# CC2541A.net
KiCad netlist of a schematic drawn in Altium Designer
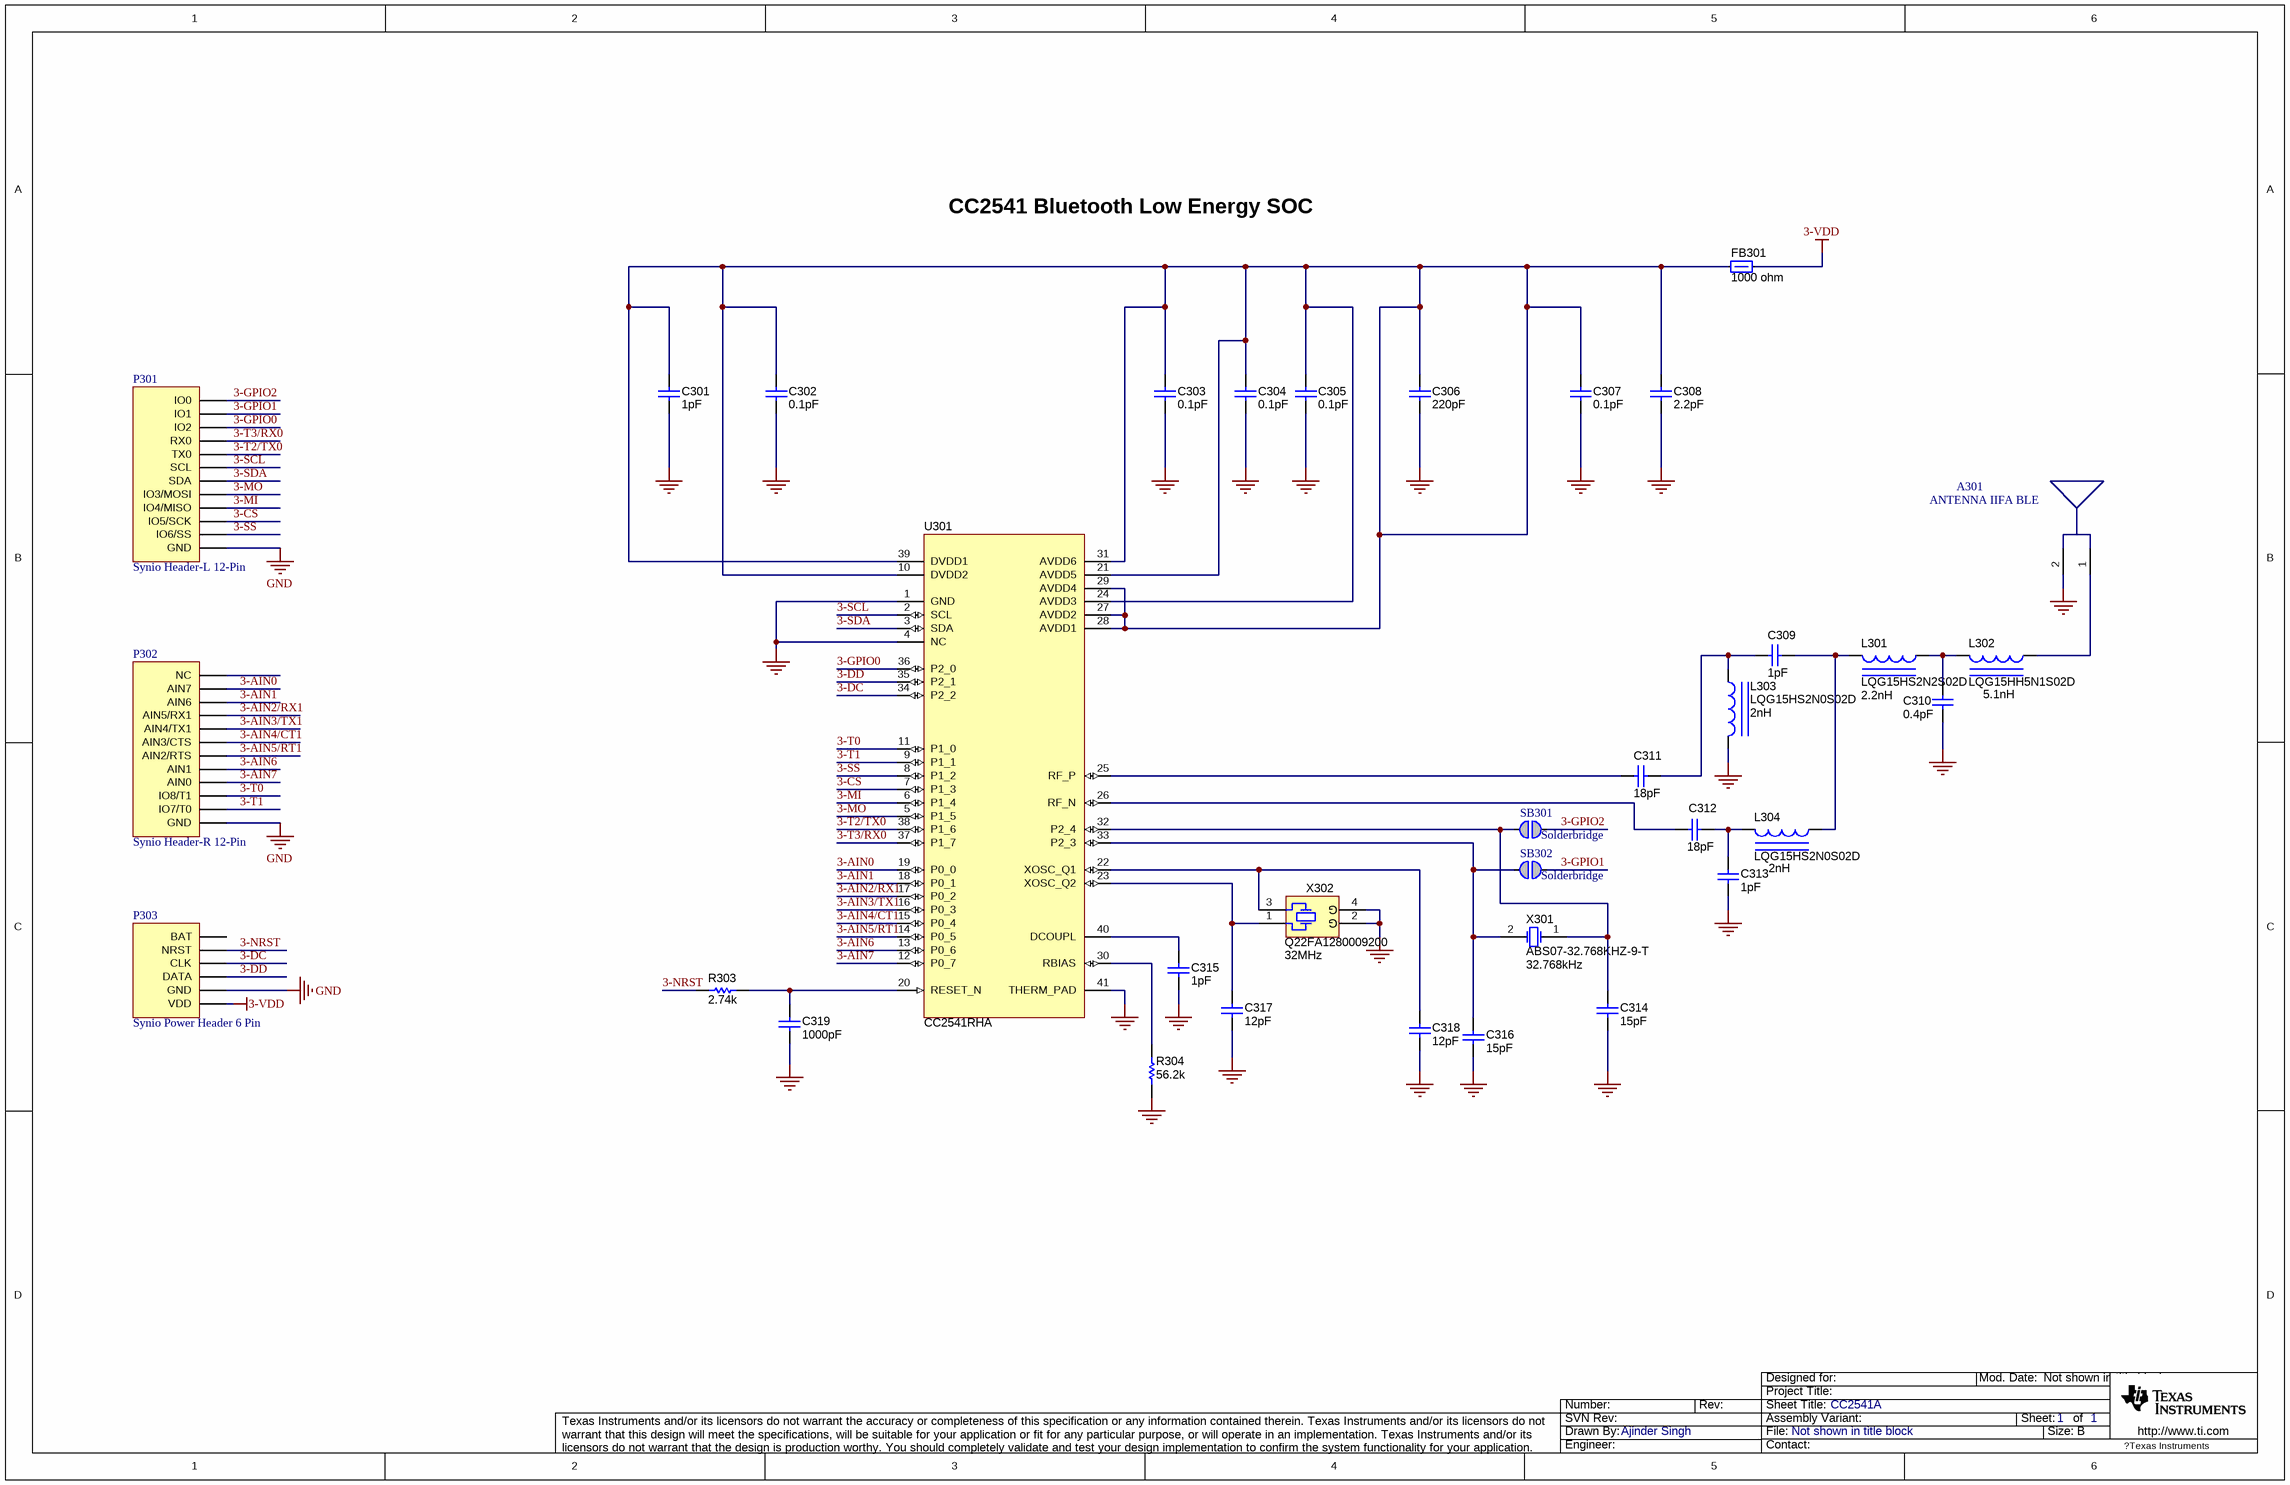
[diagram p0: CC2541A.SchDoc]

(export (version "E")
  (design (tool "Eeschema 10.0.6"))
  (components
    (comp (ref "A301")
      (value "ANTENNA IIFA BLE")
      (footprint "Antenna_IIFA_BLE-2")
      (libsource (lib "Schematic_Library") (part "ANTENNA"))
    )
    (comp (ref "C301")
      (value "C1005X5R0J105M")
      (footprint "0402L")
      (description "CAP, CERM, 1uF, 6.3V, +/-20%, X5R, 0402")
      (fields
        (field (name "VALUEDISPLAYED") "1pF")
        (field (name "MANUFACTURER") "TDK")
        (field (name "PUBLISHER") "Texas Instruments")
      )
      (libsource (lib "Capacitor_Ceramic") (part "C1005X5R0J105M"))
    )
    (comp (ref "C302")
      (value "GRM155R71A104KA01D")
      (footprint "0402L")
      (description "CAP, CERM, 0.1uF, 10V, +/-10%, X7R, 0402")
      (fields
        (field (name "VALUEDISPLAYED") "0.1pF")
        (field (name "MANUFACTURER") "MuRata")
        (field (name "PUBLISHER") "Texas Instruments")
      )
      (libsource (lib "Capacitor_Ceramic") (part "GRM155R71A104KA01D"))
    )
    (comp (ref "C303")
      (value "GRM155R71A104KA01D")
      (footprint "0402L")
      (description "CAP, CERM, 0.1uF, 10V, +/-10%, X7R, 0402")
      (fields
        (field (name "VALUEDISPLAYED") "0.1pF")
        (field (name "MANUFACTURER") "MuRata")
        (field (name "PUBLISHER") "Texas Instruments")
      )
      (libsource (lib "Capacitor_Ceramic") (part "GRM155R71A104KA01D"))
    )
    (comp (ref "C304")
      (value "GRM155R71A104KA01D")
      (footprint "0402L")
      (description "CAP, CERM, 0.1uF, 10V, +/-10%, X7R, 0402")
      (fields
        (field (name "VALUEDISPLAYED") "0.1pF")
        (field (name "MANUFACTURER") "MuRata")
        (field (name "PUBLISHER") "Texas Instruments")
      )
      (libsource (lib "Capacitor_Ceramic") (part "GRM155R71A104KA01D"))
    )
    (comp (ref "C305")
      (value "GRM155R71A104KA01D")
      (footprint "0402L")
      (description "CAP, CERM, 0.1uF, 10V, +/-10%, X7R, 0402")
      (fields
        (field (name "VALUEDISPLAYED") "0.1pF")
        (field (name "MANUFACTURER") "MuRata")
        (field (name "PUBLISHER") "Texas Instruments")
      )
      (libsource (lib "Capacitor_Ceramic") (part "GRM155R71A104KA01D"))
    )
    (comp (ref "C306")
      (value "GRM1555C1H221JA01D")
      (footprint "0402L")
      (description "CAP, CERM, 220pF, 50V, +/-5%, C0G/NP0, 0402")
      (fields
        (field (name "VALUEDISPLAYED") "220pF")
        (field (name "MANUFACTURER") "MuRata")
        (field (name "PUBLISHER") "Texas Instruments")
      )
      (libsource (lib "Capacitor_Ceramic") (part "GRM1555C1H221JA01D"))
    )
    (comp (ref "C307")
      (value "GRM155R71A104KA01D")
      (footprint "0402L")
      (description "CAP, CERM, 0.1uF, 10V, +/-10%, X7R, 0402")
      (fields
        (field (name "VALUEDISPLAYED") "0.1pF")
        (field (name "MANUFACTURER") "MuRata")
        (field (name "PUBLISHER") "Texas Instruments")
      )
      (libsource (lib "Capacitor_Ceramic") (part "GRM155R71A104KA01D"))
    )
    (comp (ref "C308")
      (value "JMK105BJ225MV-F")
      (footprint "0402L")
      (description "CAP, CERM, 2.2uF, 6.3V, +/-20%, X5R, 0402")
      (fields
        (field (name "VALUEDISPLAYED") "2.2pF")
        (field (name "MANUFACTURER") "Taiyo Yuden")
        (field (name "PUBLISHER") "Texas Instruments")
      )
      (libsource (lib "Capacitor_Ceramic") (part "JMK105BJ225MV-F"))
    )
    (comp (ref "C309")
      (value "GRM1555C1H1R0CA01D")
      (footprint "0402L")
      (description "CAP, CERM, 1pF, 50V, +/-5%, C0G/NP0, 0402")
      (fields
        (field (name "VALUEDISPLAYED") "1pF")
        (field (name "MANUFACTURER") "MuRata")
        (field (name "PUBLISHER") "Texas Instruments")
      )
      (libsource (lib "Capacitor_Ceramic") (part "GRM1555C1H1R0CA01D"))
    )
    (comp (ref "C310")
      (value "GRM1555C1HR40BA01D")
      (footprint "0402L")
      (description "CAP, CERM, 0.4pF, 50V, +/-25%, C0G/NP0, 0402")
      (fields
        (field (name "VALUEDISPLAYED") "0.4pF")
        (field (name "MANUFACTURER") "MuRata")
        (field (name "PUBLISHER") "Texas Instruments")
      )
      (libsource (lib "Capacitor_Ceramic") (part "GRM1555C1HR40BA01D"))
    )
    (comp (ref "C311")
      (value "GRM1555C1H180JA01D")
      (footprint "0402L")
      (description "CAP, CERM, 18pF, 50V, +/-5%, C0G/NP0, 0402")
      (fields
        (field (name "VALUEDISPLAYED") "18pF")
        (field (name "MANUFACTURER") "MuRata")
        (field (name "PUBLISHER") "Texas Instruments")
      )
      (libsource (lib "Capacitor_Ceramic") (part "GRM1555C1H180JA01D"))
    )
    (comp (ref "C312")
      (value "GRM1555C1H180JA01D")
      (footprint "0402L")
      (description "CAP, CERM, 18pF, 50V, +/-5%, C0G/NP0, 0402")
      (fields
        (field (name "VALUEDISPLAYED") "18pF")
        (field (name "MANUFACTURER") "MuRata")
        (field (name "PUBLISHER") "Texas Instruments")
      )
      (libsource (lib "Capacitor_Ceramic") (part "GRM1555C1H180JA01D"))
    )
    (comp (ref "C313")
      (value "GRM1555C1H1R0CA01D")
      (footprint "0402L")
      (description "CAP, CERM, 1pF, 50V, +/-5%, C0G/NP0, 0402")
      (fields
        (field (name "VALUEDISPLAYED") "1pF")
        (field (name "MANUFACTURER") "MuRata")
        (field (name "PUBLISHER") "Texas Instruments")
      )
      (libsource (lib "Capacitor_Ceramic") (part "GRM1555C1H1R0CA01D"))
    )
    (comp (ref "C314")
      (value "GRM1555C1H150JA01D")
      (footprint "0402L")
      (description "CAP, CERM, 15pF, 50V, +/-5%, C0G/NP0, 0402")
      (fields
        (field (name "VALUEDISPLAYED") "15pF")
        (field (name "MANUFACTURER") "MuRata")
        (field (name "PUBLISHER") "Texas Instruments")
      )
      (libsource (lib "Capacitor_Ceramic") (part "GRM1555C1H150JA01D"))
    )
    (comp (ref "C315")
      (value "C1005X5R0J105M")
      (footprint "0402L")
      (description "CAP, CERM, 1uF, 6.3V, +/-20%, X5R, 0402")
      (fields
        (field (name "VALUEDISPLAYED") "1pF")
        (field (name "MANUFACTURER") "TDK")
        (field (name "PUBLISHER") "Texas Instruments")
      )
      (libsource (lib "Capacitor_Ceramic") (part "C1005X5R0J105M"))
    )
    (comp (ref "C316")
      (value "GRM1555C1H150JA01D")
      (footprint "0402L")
      (description "CAP, CERM, 15pF, 50V, +/-5%, C0G/NP0, 0402")
      (fields
        (field (name "VALUEDISPLAYED") "15pF")
        (field (name "MANUFACTURER") "MuRata")
        (field (name "PUBLISHER") "Texas Instruments")
      )
      (libsource (lib "Capacitor_Ceramic") (part "GRM1555C1H150JA01D"))
    )
    (comp (ref "C317")
      (value "GRM1555C1H120JA01D")
      (footprint "0402L")
      (description "CAP, CERM, 12pF, 50V, +/-5%, C0G/NP0, 0402")
      (fields
        (field (name "VALUEDISPLAYED") "12pF")
        (field (name "MANUFACTURER") "MuRata")
        (field (name "PUBLISHER") "Texas Instruments")
      )
      (libsource (lib "Capacitor_Ceramic") (part "GRM1555C1H120JA01D"))
    )
    (comp (ref "C318")
      (value "GRM1555C1H120JA01D")
      (footprint "0402L")
      (description "CAP, CERM, 12pF, 50V, +/-5%, C0G/NP0, 0402")
      (fields
        (field (name "VALUEDISPLAYED") "12pF")
        (field (name "MANUFACTURER") "MuRata")
        (field (name "PUBLISHER") "Texas Instruments")
      )
      (libsource (lib "Capacitor_Ceramic") (part "GRM1555C1H120JA01D"))
    )
    (comp (ref "C319")
      (value "GRM1555C1H102JA01D")
      (footprint "0402L")
      (description "CAP, CERM, 1000pF, 50V, +/-5%, C0G/NP0, 0402")
      (fields
        (field (name "VALUEDISPLAYED") "1000pF")
        (field (name "MANUFACTURER") "MuRata")
        (field (name "PUBLISHER") "Texas Instruments")
      )
      (libsource (lib "Capacitor_Ceramic") (part "GRM1555C1H102JA01D"))
    )
    (comp (ref "FB301")
      (value "1000 ohm")
      (footprint "0402")
      (description "0.25A Ferrite Bead, 1000 ohm @ 100MHz, SMD")
      (fields
        (field (name "PARTNUMBER") "BLM15HG102SN1D")
        (field (name "MANUFACTURER") "MuRata")
        (field (name "PUBLISHER") "Texas Instruments")
      )
      (libsource (lib "Inductor") (part "BLM15HG102SN1D"))
    )
    (comp (ref "L301")
      (value "LQG15HS2N2S02D")
      (footprint "IND_LQG15H")
      (description "Inductor, Multilayer, Air Core, 2.2nH, 0.3A, 0.12 ohm, SMD")
      (fields
        (field (name "VALUEDISPLAYED") "2.2nH")
        (field (name "MANUFACTURER") "MuRata")
        (field (name "PUBLISHER") "Texas Instruments")
      )
      (libsource (lib "Inductor") (part "LQG15HS2N2S02D"))
    )
    (comp (ref "L302")
      (value "LQG15HH5N1S02D")
      (footprint "0402L")
      (description "Inductor, Multilayer, Ferrite, 5.1nH, 0.3A, 0.2 ohm, SMD")
      (fields
        (field (name "VALUEDISPLAYED") "5.1nH")
        (field (name "MANUFACTURER") "MuRata")
        (field (name "PUBLISHER") "Texas Instruments")
      )
      (libsource (lib "Inductor") (part "LQG15HH5N1S02D"))
    )
    (comp (ref "L303")
      (value "LQG15HS2N0S02D")
      (footprint "0402L")
      (description "Inductor, Multilayer, Ferrite, 2nH, 0.3A, 0.1 ohm, SMD")
      (fields
        (field (name "VALUEDISPLAYED") "2nH")
        (field (name "MANUFACTURER") "MuRata")
        (field (name "PUBLISHER") "Texas Instruments")
      )
      (libsource (lib "Inductor") (part "LQG15HS2N0S02D"))
    )
    (comp (ref "L304")
      (value "LQG15HS2N0S02D")
      (footprint "0402L")
      (description "Inductor, Multilayer, Ferrite, 2nH, 0.3A, 0.1 ohm, SMD")
      (fields
        (field (name "VALUEDISPLAYED") "2nH")
        (field (name "MANUFACTURER") "MuRata")
        (field (name "PUBLISHER") "Texas Instruments")
      )
      (libsource (lib "Inductor") (part "LQG15HS2N0S02D"))
    )
    (comp (ref "P301")
      (value "Synio Header-L 12-Pin")
      (footprint "HDR1X12")
      (description "Synio Header-L, 12-Pin")
      (fields (field (name "PUBLISHER") "Altium Limited"))
      (libsource (lib "Connector") (part "Synio Header-L 12-Pin"))
    )
    (comp (ref "P302")
      (value "Synio Header-R 12-Pin")
      (footprint "HDR1X12")
      (description "Synio Header-R, 12-Pin")
      (fields (field (name "PUBLISHER") "Altium Limited"))
      (libsource (lib "Connector") (part "Synio Header-R 12-Pin"))
    )
    (comp (ref "P303")
      (value "Synio Power Header 6 Pin")
      (footprint "HDR1X6/2.54MM")
      (libsource (lib "Connector") (part "Synio Power Header 6 Pin"))
    )
    (comp (ref "R303")
      (value "2.74k")
      (footprint "0402L")
      (description "RES, 2.74k ohm, 1%, 0.063W, 0402")
      (fields
        (field (name "PARTNUMBER") "CRCW04022K74FKED")
        (field (name "MANUFACTURER") "Vishay-Dale")
        (field (name "PUBLISHER") "Texas Instruments")
      )
      (libsource (lib "Resistor_0402") (part "CRCW04022K74FKED"))
    )
    (comp (ref "R304")
      (value "56.2k")
      (footprint "0402L")
      (description "RES, 56.2k ohm, 1%, 0.063W, 0402")
      (fields
        (field (name "PARTNUMBER") "CRCW040256K2FKED")
        (field (name "MANUFACTURER") "Vishay-Dale")
        (field (name "PUBLISHER") "Texas Instruments")
      )
      (libsource (lib "Resistor_0402") (part "CRCW040256K2FKED"))
    )
    (comp (ref "SB301")
      (value "Solderbridge")
      (footprint "JP2_SMD")
      (fields (field (name "PUBLISHER") "Nordic Semiconductor"))
      (libsource (lib "Nordic Passive DB") (part "SOLDERBRIDGE"))
    )
    (comp (ref "SB302")
      (value "Solderbridge")
      (footprint "JP2_SMD")
      (fields (field (name "PUBLISHER") "Nordic Semiconductor"))
      (libsource (lib "Nordic Passive DB") (part "SOLDERBRIDGE"))
    )
    (comp (ref "U301")
      (value "CC2541RHA")
      (footprint "RHA0040H")
      (description "2.4-GHz Bluetooth low energy and Proprietary System-on-Chip, RHA0040H")
      (fields
        (field (name "MANUFACTURER") "Texas Instruments")
        (field (name "SYMBOLCREATOR") "a0411947")
        (field (name "PUBLISHER") "Texas Instruments")
      )
      (libsource (lib "TI_Pre_Release") (part "CC2541RHA"))
    )
    (comp (ref "X301")
      (value "ABS07-32.768KHZ-9-T")
      (footprint "XTAL_ABS07")
      (description "CRYSTAL, 32.768KHZ, 9PF, SMD")
      (fields
        (field (name "FREQUENCY") "32.768kHz")
        (field (name "MANUFACTURER") "Abracon Corportation")
        (field (name "SYMBOLCREATOR") "a0412235")
        (field (name "PUBLISHER") "Texas Instruments")
      )
      (libsource (lib "Oscillators") (part "ABS07-32.768KHZ-9-T"))
    )
    (comp (ref "X302")
      (value "Q22FA1280009200")
      (footprint "XTAL_FA-128")
      (description "Crystal, 32MHz, 10pF, SMD")
      (fields
        (field (name "FREQUENCY") "32MHz")
        (field (name "MANUFACTURER") "Epson")
        (field (name "SYMBOLCREATOR") "a0412235")
        (field (name "PUBLISHER") "Texas Instruments")
      )
      (libsource (lib "Oscillators") (part "Q22FA1280009200"))
    )
  )
  (nets
    (net (code "1") (name "/3-AIN0") (class "Default")
      (node (ref "P302") (pin "11") (pinfunction "AIN7_11") (pintype "passive"))
      (node (ref "U301") (pin "19") (pinfunction "P0_0_19") (pintype "bidirectional"))
    )
    (net (code "2") (name "/3-AIN1") (class "Default")
      (node (ref "P302") (pin "10") (pinfunction "AIN6_10") (pintype "passive"))
      (node (ref "U301") (pin "18") (pinfunction "P0_1_18") (pintype "bidirectional"))
    )
    (net (code "3") (name "/3-AIN2{slash}RX1") (class "Default")
      (node (ref "P302") (pin "9") (pinfunction "AIN5/RX1_9") (pintype "passive"))
      (node (ref "U301") (pin "17") (pinfunction "P0_2_17") (pintype "bidirectional"))
    )
    (net (code "4") (name "/3-AIN3{slash}TX1") (class "Default")
      (node (ref "P302") (pin "8") (pinfunction "AIN4/TX1_8") (pintype "passive"))
      (node (ref "U301") (pin "16") (pinfunction "P0_3_16") (pintype "bidirectional"))
    )
    (net (code "5") (name "/3-AIN4{slash}CT1") (class "Default")
      (node (ref "P302") (pin "7") (pinfunction "AIN3/CTS_7") (pintype "passive"))
      (node (ref "U301") (pin "15") (pinfunction "P0_4_15") (pintype "bidirectional"))
    )
    (net (code "6") (name "/3-AIN5{slash}RT1") (class "Default")
      (node (ref "P302") (pin "6") (pinfunction "AIN2/RTS_6") (pintype "passive"))
      (node (ref "U301") (pin "14") (pinfunction "P0_5_14") (pintype "bidirectional"))
    )
    (net (code "7") (name "/3-AIN6") (class "Default")
      (node (ref "P302") (pin "5") (pinfunction "AIN1_5") (pintype "passive"))
      (node (ref "U301") (pin "13") (pinfunction "P0_6_13") (pintype "bidirectional"))
    )
    (net (code "8") (name "/3-AIN7") (class "Default")
      (node (ref "P302") (pin "4") (pinfunction "AIN0_4") (pintype "passive"))
      (node (ref "U301") (pin "12") (pinfunction "P0_7_12") (pintype "bidirectional"))
    )
    (net (code "9") (name "/3-CS") (class "Default")
      (node (ref "P301") (pin "3") (pinfunction "IO5/SCK_3") (pintype "passive"))
      (node (ref "U301") (pin "7") (pinfunction "P1_3_7") (pintype "bidirectional"))
    )
    (net (code "10") (name "/3-DC") (class "Default")
      (node (ref "P303") (pin "4") (pinfunction "CLK_4") (pintype "passive"))
      (node (ref "U301") (pin "34") (pinfunction "P2_2_34") (pintype "bidirectional"))
    )
    (net (code "11") (name "/3-DD") (class "Default")
      (node (ref "P303") (pin "3") (pinfunction "DATA_3") (pintype "passive"))
      (node (ref "U301") (pin "35") (pinfunction "P2_1_35") (pintype "bidirectional"))
    )
    (net (code "12") (name "/3-GPIO0") (class "Default")
      (node (ref "P301") (pin "10") (pinfunction "IO2_10") (pintype "passive"))
      (node (ref "U301") (pin "36") (pinfunction "P2_0_36") (pintype "bidirectional"))
    )
    (net (code "13") (name "/3-GPIO1") (class "Default")
      (node (ref "P301") (pin "11") (pinfunction "IO1_11") (pintype "passive"))
      (node (ref "SB302") (pin "1") (pinfunction "0_1") (pintype "passive"))
    )
    (net (code "14") (name "/3-GPIO2") (class "Default")
      (node (ref "P301") (pin "12") (pinfunction "IO0_12") (pintype "passive"))
      (node (ref "SB301") (pin "1") (pinfunction "0_1") (pintype "passive"))
    )
    (net (code "15") (name "/3-MI") (class "Default")
      (node (ref "P301") (pin "4") (pinfunction "IO4/MISO_4") (pintype "passive"))
      (node (ref "U301") (pin "6") (pinfunction "P1_4_6") (pintype "bidirectional"))
    )
    (net (code "16") (name "/3-MO") (class "Default")
      (node (ref "P301") (pin "5") (pinfunction "IO3/MOSI_5") (pintype "passive"))
      (node (ref "U301") (pin "5") (pinfunction "P1_5_5") (pintype "bidirectional"))
    )
    (net (code "17") (name "/3-NRST") (class "Default")
      (node (ref "P303") (pin "5") (pinfunction "NRST_5") (pintype "passive"))
      (node (ref "R303") (pin "1") (pinfunction "1_1") (pintype "passive"))
    )
    (net (code "18") (name "/3-SCL") (class "Default")
      (node (ref "P301") (pin "7") (pinfunction "SCL_7") (pintype "passive"))
      (node (ref "U301") (pin "2") (pinfunction "SCL_2") (pintype "bidirectional"))
    )
    (net (code "19") (name "/3-SDA") (class "Default")
      (node (ref "P301") (pin "6") (pinfunction "SDA_6") (pintype "passive"))
      (node (ref "U301") (pin "3") (pinfunction "SDA_3") (pintype "bidirectional"))
    )
    (net (code "20") (name "/3-SS") (class "Default")
      (node (ref "P301") (pin "2") (pinfunction "IO6/SS_2") (pintype "passive"))
      (node (ref "U301") (pin "8") (pinfunction "P1_2_8") (pintype "bidirectional"))
    )
    (net (code "21") (name "/3-T0") (class "Default")
      (node (ref "P302") (pin "3") (pinfunction "IO8/T1_3") (pintype "passive"))
      (node (ref "U301") (pin "11") (pinfunction "P1_0_11") (pintype "bidirectional"))
    )
    (net (code "22") (name "/3-T1") (class "Default")
      (node (ref "P302") (pin "2") (pinfunction "IO7/T0_2") (pintype "passive"))
      (node (ref "U301") (pin "9") (pinfunction "P1_1_9") (pintype "bidirectional"))
    )
    (net (code "23") (name "/3-T2{slash}TX0") (class "Default")
      (node (ref "P301") (pin "8") (pinfunction "TX0_8") (pintype "passive"))
      (node (ref "U301") (pin "38") (pinfunction "P1_6_38") (pintype "bidirectional"))
    )
    (net (code "24") (name "/3-T3{slash}RX0") (class "Default")
      (node (ref "P301") (pin "9") (pinfunction "RX0_9") (pintype "passive"))
      (node (ref "U301") (pin "37") (pinfunction "P1_7_37") (pintype "bidirectional"))
    )
    (net (code "25") (name "3-VDD") (class "Default")
      (node (ref "FB301") (pin "2") (pinfunction "2_2") (pintype "passive"))
      (node (ref "P303") (pin "1") (pinfunction "VDD_1") (pintype "passive"))
    )
    (net (code "26") (name "GND") (class "Default")
      (node (ref "A301") (pin "2") (pinfunction "2_2") (pintype "passive"))
      (node (ref "C301") (pin "2") (pinfunction "2_2") (pintype "passive"))
      (node (ref "C302") (pin "2") (pinfunction "2_2") (pintype "passive"))
      (node (ref "C303") (pin "2") (pinfunction "2_2") (pintype "passive"))
      (node (ref "C304") (pin "2") (pinfunction "2_2") (pintype "passive"))
      (node (ref "C305") (pin "2") (pinfunction "2_2") (pintype "passive"))
      (node (ref "C306") (pin "2") (pinfunction "2_2") (pintype "passive"))
      (node (ref "C307") (pin "2") (pinfunction "2_2") (pintype "passive"))
      (node (ref "C308") (pin "2") (pinfunction "2_2") (pintype "passive"))
      (node (ref "C310") (pin "2") (pinfunction "2_2") (pintype "passive"))
      (node (ref "C313") (pin "2") (pinfunction "2_2") (pintype "passive"))
      (node (ref "C314") (pin "2") (pinfunction "2_2") (pintype "passive"))
      (node (ref "C315") (pin "2") (pinfunction "2_2") (pintype "passive"))
      (node (ref "C316") (pin "2") (pinfunction "2_2") (pintype "passive"))
      (node (ref "C317") (pin "2") (pinfunction "2_2") (pintype "passive"))
      (node (ref "C318") (pin "2") (pinfunction "2_2") (pintype "passive"))
      (node (ref "C319") (pin "2") (pinfunction "2_2") (pintype "passive"))
      (node (ref "L303") (pin "2") (pinfunction "2_2") (pintype "passive"))
      (node (ref "P301") (pin "1") (pinfunction "GND_1") (pintype "passive"))
      (node (ref "P302") (pin "1") (pinfunction "GND_1") (pintype "passive"))
      (node (ref "P303") (pin "2") (pinfunction "GND_2") (pintype "passive"))
      (node (ref "R304") (pin "1") (pinfunction "1_1") (pintype "passive"))
      (node (ref "U301") (pin "1") (pinfunction "GND_1") (pintype "power_in"))
      (node (ref "U301") (pin "4") (pinfunction "NC_4") (pintype "passive"))
      (node (ref "U301") (pin "41") (pinfunction "THERM_PAD_41") (pintype "power_in"))
      (node (ref "X302") (pin "2") (pinfunction "GND_2") (pintype "power_in"))
      (node (ref "X302") (pin "4") (pinfunction "GND_4") (pintype "power_in"))
    )
    (net (code "27") (name "Net-(A301-Pad1)") (class "Default")
      (node (ref "A301") (pin "1") (pinfunction "1_1") (pintype "passive"))
      (node (ref "L302") (pin "1") (pinfunction "1_1") (pintype "passive"))
    )
    (net (code "28") (name "Net-(C309-Pad1)") (class "Default")
      (node (ref "C309") (pin "1") (pinfunction "1_1") (pintype "passive"))
      (node (ref "C311") (pin "1") (pinfunction "1_1") (pintype "passive"))
      (node (ref "L303") (pin "1") (pinfunction "1_1") (pintype "passive"))
    )
    (net (code "29") (name "Net-(C309-Pad2)") (class "Default")
      (node (ref "C309") (pin "2") (pinfunction "2_2") (pintype "passive"))
      (node (ref "L301") (pin "2") (pinfunction "2_2") (pintype "passive"))
      (node (ref "L304") (pin "1") (pinfunction "1_1") (pintype "passive"))
    )
    (net (code "30") (name "Net-(C310-Pad1)") (class "Default")
      (node (ref "C310") (pin "1") (pinfunction "1_1") (pintype "passive"))
      (node (ref "L301") (pin "1") (pinfunction "1_1") (pintype "passive"))
      (node (ref "L302") (pin "2") (pinfunction "2_2") (pintype "passive"))
    )
    (net (code "31") (name "Net-(C312-Pad1)") (class "Default")
      (node (ref "C312") (pin "1") (pinfunction "1_1") (pintype "passive"))
      (node (ref "C313") (pin "1") (pinfunction "1_1") (pintype "passive"))
      (node (ref "L304") (pin "2") (pinfunction "2_2") (pintype "passive"))
    )
    (net (code "32") (name "Net-(SB301-1)") (class "Default")
      (node (ref "C314") (pin "1") (pinfunction "1_1") (pintype "passive"))
      (node (ref "SB301") (pin "2") (pinfunction "1_2") (pintype "passive"))
      (node (ref "U301") (pin "32") (pinfunction "P2_4_32") (pintype "bidirectional"))
      (node (ref "X301") (pin "1") (pinfunction "OSC1_1") (pintype "passive"))
    )
    (net (code "33") (name "Net-(SB302-1)") (class "Default")
      (node (ref "C316") (pin "1") (pinfunction "1_1") (pintype "passive"))
      (node (ref "SB302") (pin "2") (pinfunction "1_2") (pintype "passive"))
      (node (ref "U301") (pin "33") (pinfunction "P2_3_33") (pintype "bidirectional"))
      (node (ref "X301") (pin "2") (pinfunction "OSC2_2") (pintype "passive"))
    )
    (net (code "34") (name "Net-(U301-AVDD1)") (class "Default")
      (node (ref "C301") (pin "1") (pinfunction "1_1") (pintype "passive"))
      (node (ref "C302") (pin "1") (pinfunction "1_1") (pintype "passive"))
      (node (ref "C303") (pin "1") (pinfunction "1_1") (pintype "passive"))
      (node (ref "C304") (pin "1") (pinfunction "1_1") (pintype "passive"))
      (node (ref "C305") (pin "1") (pinfunction "1_1") (pintype "passive"))
      (node (ref "C306") (pin "1") (pinfunction "1_1") (pintype "passive"))
      (node (ref "C307") (pin "1") (pinfunction "1_1") (pintype "passive"))
      (node (ref "C308") (pin "1") (pinfunction "1_1") (pintype "passive"))
      (node (ref "FB301") (pin "1") (pinfunction "1_1") (pintype "passive"))
      (node (ref "U301") (pin "10") (pinfunction "DVDD2_10") (pintype "power_in"))
      (node (ref "U301") (pin "21") (pinfunction "AVDD5_21") (pintype "power_in"))
      (node (ref "U301") (pin "24") (pinfunction "AVDD3_24") (pintype "power_in"))
      (node (ref "U301") (pin "27") (pinfunction "AVDD2_27") (pintype "power_in"))
      (node (ref "U301") (pin "28") (pinfunction "AVDD1_28") (pintype "power_in"))
      (node (ref "U301") (pin "29") (pinfunction "AVDD4_29") (pintype "power_in"))
      (node (ref "U301") (pin "31") (pinfunction "AVDD6_31") (pintype "power_in"))
      (node (ref "U301") (pin "39") (pinfunction "DVDD1_39") (pintype "power_in"))
    )
    (net (code "35") (name "Net-(U301-DCOUPL)") (class "Default")
      (node (ref "C315") (pin "1") (pinfunction "1_1") (pintype "passive"))
      (node (ref "U301") (pin "40") (pinfunction "DCOUPL_40") (pintype "power_in"))
    )
    (net (code "36") (name "Net-(U301-RBIAS)") (class "Default")
      (node (ref "R304") (pin "2") (pinfunction "2_2") (pintype "passive"))
      (node (ref "U301") (pin "30") (pinfunction "RBIAS_30") (pintype "bidirectional"))
    )
    (net (code "37") (name "Net-(U301-RESET_N)") (class "Default")
      (node (ref "C319") (pin "1") (pinfunction "1_1") (pintype "passive"))
      (node (ref "R303") (pin "2") (pinfunction "2_2") (pintype "passive"))
      (node (ref "U301") (pin "20") (pinfunction "RESET_N_20") (pintype "input"))
    )
    (net (code "38") (name "Net-(U301-RF_N)") (class "Default")
      (node (ref "C312") (pin "2") (pinfunction "2_2") (pintype "passive"))
      (node (ref "U301") (pin "26") (pinfunction "RF_N_26") (pintype "bidirectional"))
    )
    (net (code "39") (name "Net-(U301-RF_P)") (class "Default")
      (node (ref "C311") (pin "2") (pinfunction "2_2") (pintype "passive"))
      (node (ref "U301") (pin "25") (pinfunction "RF_P_25") (pintype "bidirectional"))
    )
    (net (code "40") (name "Net-(U301-XOSC_Q1)") (class "Default")
      (node (ref "C318") (pin "1") (pinfunction "1_1") (pintype "passive"))
      (node (ref "U301") (pin "22") (pinfunction "XOSC_Q1_22") (pintype "bidirectional"))
      (node (ref "X302") (pin "3") (pinfunction "3_3") (pintype "passive"))
    )
    (net (code "41") (name "Net-(U301-XOSC_Q2)") (class "Default")
      (node (ref "C317") (pin "1") (pinfunction "1_1") (pintype "passive"))
      (node (ref "U301") (pin "23") (pinfunction "XOSC_Q2_23") (pintype "bidirectional"))
      (node (ref "X302") (pin "1") (pinfunction "1_1") (pintype "passive"))
    )
    (net (code "42") (name "unconnected-(P302-NC-Pad12)") (class "Default")
      (node (ref "P302") (pin "12") (pinfunction "NC_12") (pintype "passive"))
    )
    (net (code "43") (name "unconnected-(P303-BAT-Pad6)") (class "Default")
      (node (ref "P303") (pin "6") (pinfunction "BAT_6") (pintype "passive"))
    )
  )
)
